# F-Cable.net
KiCad netlist of a schematic drawn in EAGLE
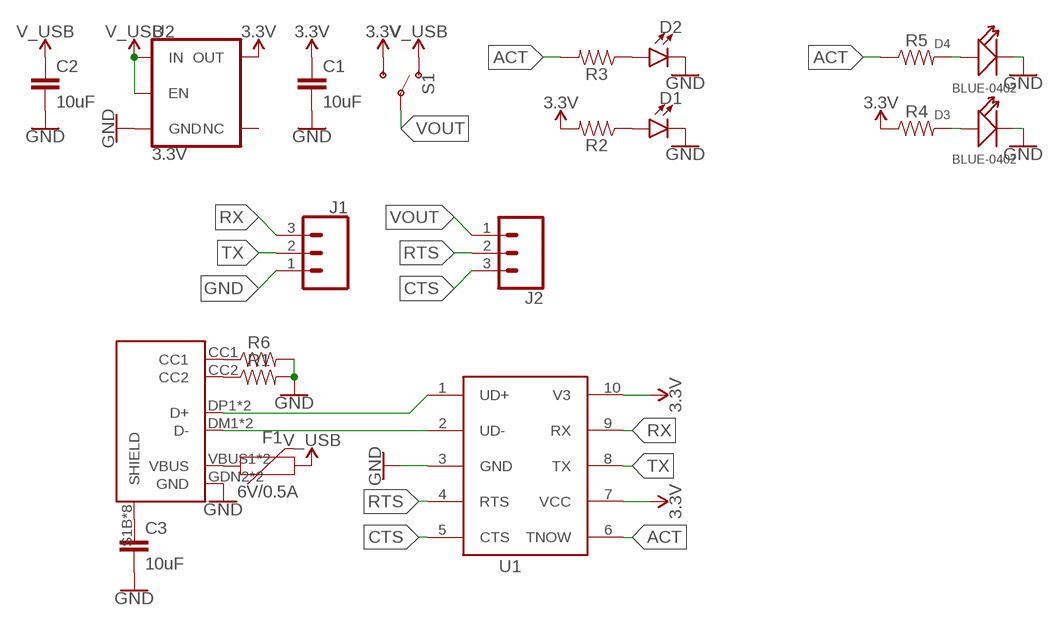
[diagram p0: schematic, sheet 1]

(export (version "E")
  (design (tool "Eeschema 10.0.6"))
  (components
    (comp (ref "C1")
      (value "10uF")
      (footprint "eagle-import:0603")
      (libsource (lib "eagle-import") (part "10UF-0603-6.3V-20%"))
    )
    (comp (ref "C2")
      (value "10uF")
      (footprint "eagle-import:0603")
      (libsource (lib "eagle-import") (part "10UF-0603-6.3V-20%"))
    )
    (comp (ref "C3")
      (value "10uF")
      (footprint "eagle-import:0603")
      (libsource (lib "eagle-import") (part "10UF-0603-6.3V-20%"))
    )
    (comp (ref "D1")
      (value "LED0603")
      (footprint "eagle-import:LED-0603")
      (libsource (lib "eagle-import") (part "LED0603"))
    )
    (comp (ref "D2")
      (value "LED0603")
      (footprint "eagle-import:LED-0603")
      (libsource (lib "eagle-import") (part "LED0603"))
    )
    (comp (ref "D3")
      (value "BLUE-0402")
      (footprint "eagle-import:LED-0402")
      (fields (field (name "MPN") "BL-HB337A-AV-TRB"))
      (libsource (lib "eagle-import") (part "SMD-LED-CLEAR-BLUE(0402)"))
    )
    (comp (ref "D4")
      (value "BLUE-0402")
      (footprint "eagle-import:LED-0402")
      (fields (field (name "MPN") "BL-HB337A-AV-TRB"))
      (libsource (lib "eagle-import") (part "SMD-LED-CLEAR-BLUE(0402)"))
    )
    (comp (ref "F1")
      (value "6V/0.5A")
      (footprint "eagle-import:1206")
      (libsource (lib "eagle-import") (part "PPTC_HALF-AMP"))
    )
    (comp (ref "J1")
      (value "CONN_03SMD_RA_MALE")
      (footprint "eagle-import:1X03_SMD_RA_MALE")
      (libsource (lib "eagle-import") (part "CONN_03SMD_RA_MALE"))
    )
    (comp (ref "J2")
      (value "CONN_03SMD_RA_MALE")
      (footprint "eagle-import:1X03_SMD_RA_MALE")
      (libsource (lib "eagle-import") (part "CONN_03SMD_RA_MALE"))
    )
    (comp (ref "R1")
      (value "RESISTOR0603")
      (footprint "eagle-import:0603")
      (libsource (lib "eagle-import") (part "RESISTOR0603"))
    )
    (comp (ref "R2")
      (value "RESISTOR0603")
      (footprint "eagle-import:0603")
      (libsource (lib "eagle-import") (part "RESISTOR0603"))
    )
    (comp (ref "R3")
      (value "RESISTOR0603")
      (footprint "eagle-import:0603")
      (libsource (lib "eagle-import") (part "RESISTOR0603"))
    )
    (comp (ref "R4")
      (value "RESISTOR0402")
      (footprint "eagle-import:0402")
      (libsource (lib "eagle-import") (part "RESISTOR0402"))
    )
    (comp (ref "R5")
      (value "RESISTOR0402")
      (footprint "eagle-import:0402")
      (libsource (lib "eagle-import") (part "RESISTOR0402"))
    )
    (comp (ref "R6")
      (value "RESISTOR0603")
      (footprint "eagle-import:0603")
      (libsource (lib "eagle-import") (part "RESISTOR0603"))
    )
    (comp (ref "S1")
      (value "SWITCH-SPDT-SMD-RIGHT-ANGLE")
      (footprint "eagle-import:SWITCH_SPST_SMD_A")
      (libsource (lib "eagle-import") (part "SWITCH-SPDT-SMD-RIGHT-ANGLE"))
    )
    (comp (ref "U$1")
      (value "USB-C_USB2ONLY-HORZ_F")
      (footprint "eagle-import:USB-C_12PIN_HORZ-F")
      (libsource (lib "eagle-import") (part "USB-C_USB2ONLY-HORZ_F"))
    )
    (comp (ref "U1")
      (value "CH340ESMD")
      (footprint "eagle-import:MSOP10")
      (libsource (lib "eagle-import") (part "CH340ESMD"))
    )
    (comp (ref "U2")
      (value "3.3V")
      (footprint "eagle-import:SOT23-5")
      (libsource (lib "eagle-import") (part "V_REG_AP2112K-3.3V"))
    )
  )
  (nets
    (net (code "1") (name "3.3V") (class "Default")
      (node (ref "C1") (pin "1") (pinfunction "1_1") (pintype "passive"))
      (node (ref "R2") (pin "2") (pinfunction "2_2") (pintype "passive"))
      (node (ref "R4") (pin "1") (pinfunction "1_1") (pintype "passive"))
      (node (ref "S1") (pin "3") (pinfunction "S_3") (pintype "passive"))
      (node (ref "U1") (pin "10") (pinfunction "V3_10") (pintype "power_in"))
      (node (ref "U1") (pin "7") (pinfunction "VCC_7") (pintype "power_in"))
      (node (ref "U2") (pin "5") (pinfunction "OUT_5") (pintype "passive"))
    )
    (net (code "2") (name "ACT") (class "Default")
      (node (ref "R3") (pin "2") (pinfunction "2_2") (pintype "passive"))
      (node (ref "R5") (pin "1") (pinfunction "1_1") (pintype "passive"))
      (node (ref "U1") (pin "6") (pinfunction "TNOW_6") (pintype "output"))
    )
    (net (code "3") (name "CTS") (class "Default")
      (node (ref "J2") (pin "3") (pinfunction "3_3") (pintype "passive"))
      (node (ref "U1") (pin "5") (pinfunction "CTS_5") (pintype "input"))
    )
    (net (code "4") (name "GND") (class "Default")
      (node (ref "C1") (pin "2") (pinfunction "2_2") (pintype "passive"))
      (node (ref "C2") (pin "2") (pinfunction "2_2") (pintype "passive"))
      (node (ref "C3") (pin "2") (pinfunction "2_2") (pintype "passive"))
      (node (ref "D1") (pin "C") (pinfunction "C_C") (pintype "passive"))
      (node (ref "D2") (pin "C") (pinfunction "C_C") (pintype "passive"))
      (node (ref "D3") (pin "-") (pinfunction "-_-") (pintype "passive"))
      (node (ref "D4") (pin "-") (pinfunction "-_-") (pintype "passive"))
      (node (ref "J1") (pin "1") (pinfunction "1_1") (pintype "passive"))
      (node (ref "R1") (pin "2") (pinfunction "2_2") (pintype "passive"))
      (node (ref "R6") (pin "2") (pinfunction "2_2") (pintype "passive"))
      (node (ref "U$1") (pin "GDN2") (pinfunction "GND_GDN2") (pintype "bidirectional"))
      (node (ref "U$1") (pin "GND1") (pinfunction "GND_GND1") (pintype "bidirectional"))
      (node (ref "U1") (pin "3") (pinfunction "GND_3") (pintype "power_in"))
      (node (ref "U2") (pin "2") (pinfunction "GND_2") (pintype "input"))
    )
    (net (code "5") (name "Net-(C3-Pad1)") (class "Default")
      (node (ref "C3") (pin "1") (pinfunction "1_1") (pintype "passive"))
      (node (ref "U$1") (pin "S1B") (pinfunction "SHIELD_S1B") (pintype "bidirectional"))
      (node (ref "U$1") (pin "S1T") (pinfunction "SHIELD_S1T") (pintype "bidirectional"))
      (node (ref "U$1") (pin "S2B") (pinfunction "SHIELD_S2B") (pintype "bidirectional"))
      (node (ref "U$1") (pin "S2T") (pinfunction "SHIELD_S2T") (pintype "bidirectional"))
      (node (ref "U$1") (pin "S3B") (pinfunction "SHIELD_S3B") (pintype "bidirectional"))
      (node (ref "U$1") (pin "S3T") (pinfunction "SHIELD_S3T") (pintype "bidirectional"))
      (node (ref "U$1") (pin "S4B") (pinfunction "SHIELD_S4B") (pintype "bidirectional"))
      (node (ref "U$1") (pin "S4T") (pinfunction "SHIELD_S4T") (pintype "bidirectional"))
    )
    (net (code "6") (name "Net-(D1-PadA)") (class "Default")
      (node (ref "D1") (pin "A") (pinfunction "A_A") (pintype "passive"))
      (node (ref "R2") (pin "1") (pinfunction "1_1") (pintype "passive"))
    )
    (net (code "7") (name "Net-(D2-PadA)") (class "Default")
      (node (ref "D2") (pin "A") (pinfunction "A_A") (pintype "passive"))
      (node (ref "R3") (pin "1") (pinfunction "1_1") (pintype "passive"))
    )
    (net (code "8") (name "Net-(D3-Pad+)") (class "Default")
      (node (ref "D3") (pin "+") (pinfunction "+_+") (pintype "passive"))
      (node (ref "R4") (pin "2") (pinfunction "2_2") (pintype "passive"))
    )
    (net (code "9") (name "Net-(D4-Pad+)") (class "Default")
      (node (ref "D4") (pin "+") (pinfunction "+_+") (pintype "passive"))
      (node (ref "R5") (pin "2") (pinfunction "2_2") (pintype "passive"))
    )
    (net (code "10") (name "Net-(F1-Pad1)") (class "Default")
      (node (ref "F1") (pin "1") (pinfunction "1_1") (pintype "bidirectional"))
      (node (ref "U$1") (pin "VBUS1") (pinfunction "VBUS_VBUS1") (pintype "bidirectional"))
      (node (ref "U$1") (pin "VBUS2") (pinfunction "VBUS_VBUS2") (pintype "bidirectional"))
    )
    (net (code "11") (name "Net-(R1-Pad1)") (class "Default")
      (node (ref "R1") (pin "1") (pinfunction "1_1") (pintype "passive"))
      (node (ref "U$1") (pin "CC2") (pinfunction "CC2_CC2") (pintype "bidirectional"))
    )
    (net (code "12") (name "Net-(R6-Pad1)") (class "Default")
      (node (ref "R6") (pin "1") (pinfunction "1_1") (pintype "passive"))
      (node (ref "U$1") (pin "CC1") (pinfunction "CC1_CC1") (pintype "bidirectional"))
    )
    (net (code "13") (name "Net-(U1-UD+)") (class "Default")
      (node (ref "U$1") (pin "DP1") (pinfunction "D+_DP1") (pintype "bidirectional"))
      (node (ref "U$1") (pin "DP2") (pinfunction "D+_DP2") (pintype "bidirectional"))
      (node (ref "U1") (pin "1") (pinfunction "UD+_1") (pintype "bidirectional"))
    )
    (net (code "14") (name "Net-(U1-UD-)") (class "Default")
      (node (ref "U$1") (pin "DM1") (pinfunction "D-_DM1") (pintype "bidirectional"))
      (node (ref "U$1") (pin "DM2") (pinfunction "D-_DM2") (pintype "bidirectional"))
      (node (ref "U1") (pin "2") (pinfunction "UD-_2") (pintype "bidirectional"))
    )
    (net (code "15") (name "RTS") (class "Default")
      (node (ref "J2") (pin "2") (pinfunction "2_2") (pintype "passive"))
      (node (ref "U1") (pin "4") (pinfunction "RTS_4") (pintype "output"))
    )
    (net (code "16") (name "RX") (class "Default")
      (node (ref "J1") (pin "3") (pinfunction "3_3") (pintype "passive"))
      (node (ref "U1") (pin "9") (pinfunction "RX_9") (pintype "input"))
    )
    (net (code "17") (name "TX") (class "Default")
      (node (ref "J1") (pin "2") (pinfunction "2_2") (pintype "passive"))
      (node (ref "U1") (pin "8") (pinfunction "TX_8") (pintype "output"))
    )
    (net (code "18") (name "VOUT") (class "Default")
      (node (ref "J2") (pin "1") (pinfunction "1_1") (pintype "passive"))
      (node (ref "S1") (pin "2") (pinfunction "P_2") (pintype "passive"))
    )
    (net (code "19") (name "V_USB") (class "Default")
      (node (ref "C2") (pin "1") (pinfunction "1_1") (pintype "passive"))
      (node (ref "F1") (pin "2") (pinfunction "2_2") (pintype "bidirectional"))
      (node (ref "S1") (pin "1") (pinfunction "O_1") (pintype "passive"))
      (node (ref "U2") (pin "1") (pinfunction "IN_1") (pintype "input"))
      (node (ref "U2") (pin "3") (pinfunction "EN_3") (pintype "input"))
    )
    (net (code "20") (name "unconnected-(U2-NC-Pad4)") (class "Default")
      (node (ref "U2") (pin "4") (pinfunction "NC_4") (pintype "no_connect"))
    )
  )
)
